# 08_LMS1_RF.net
KiCad netlist of a schematic drawn in Altium Designer
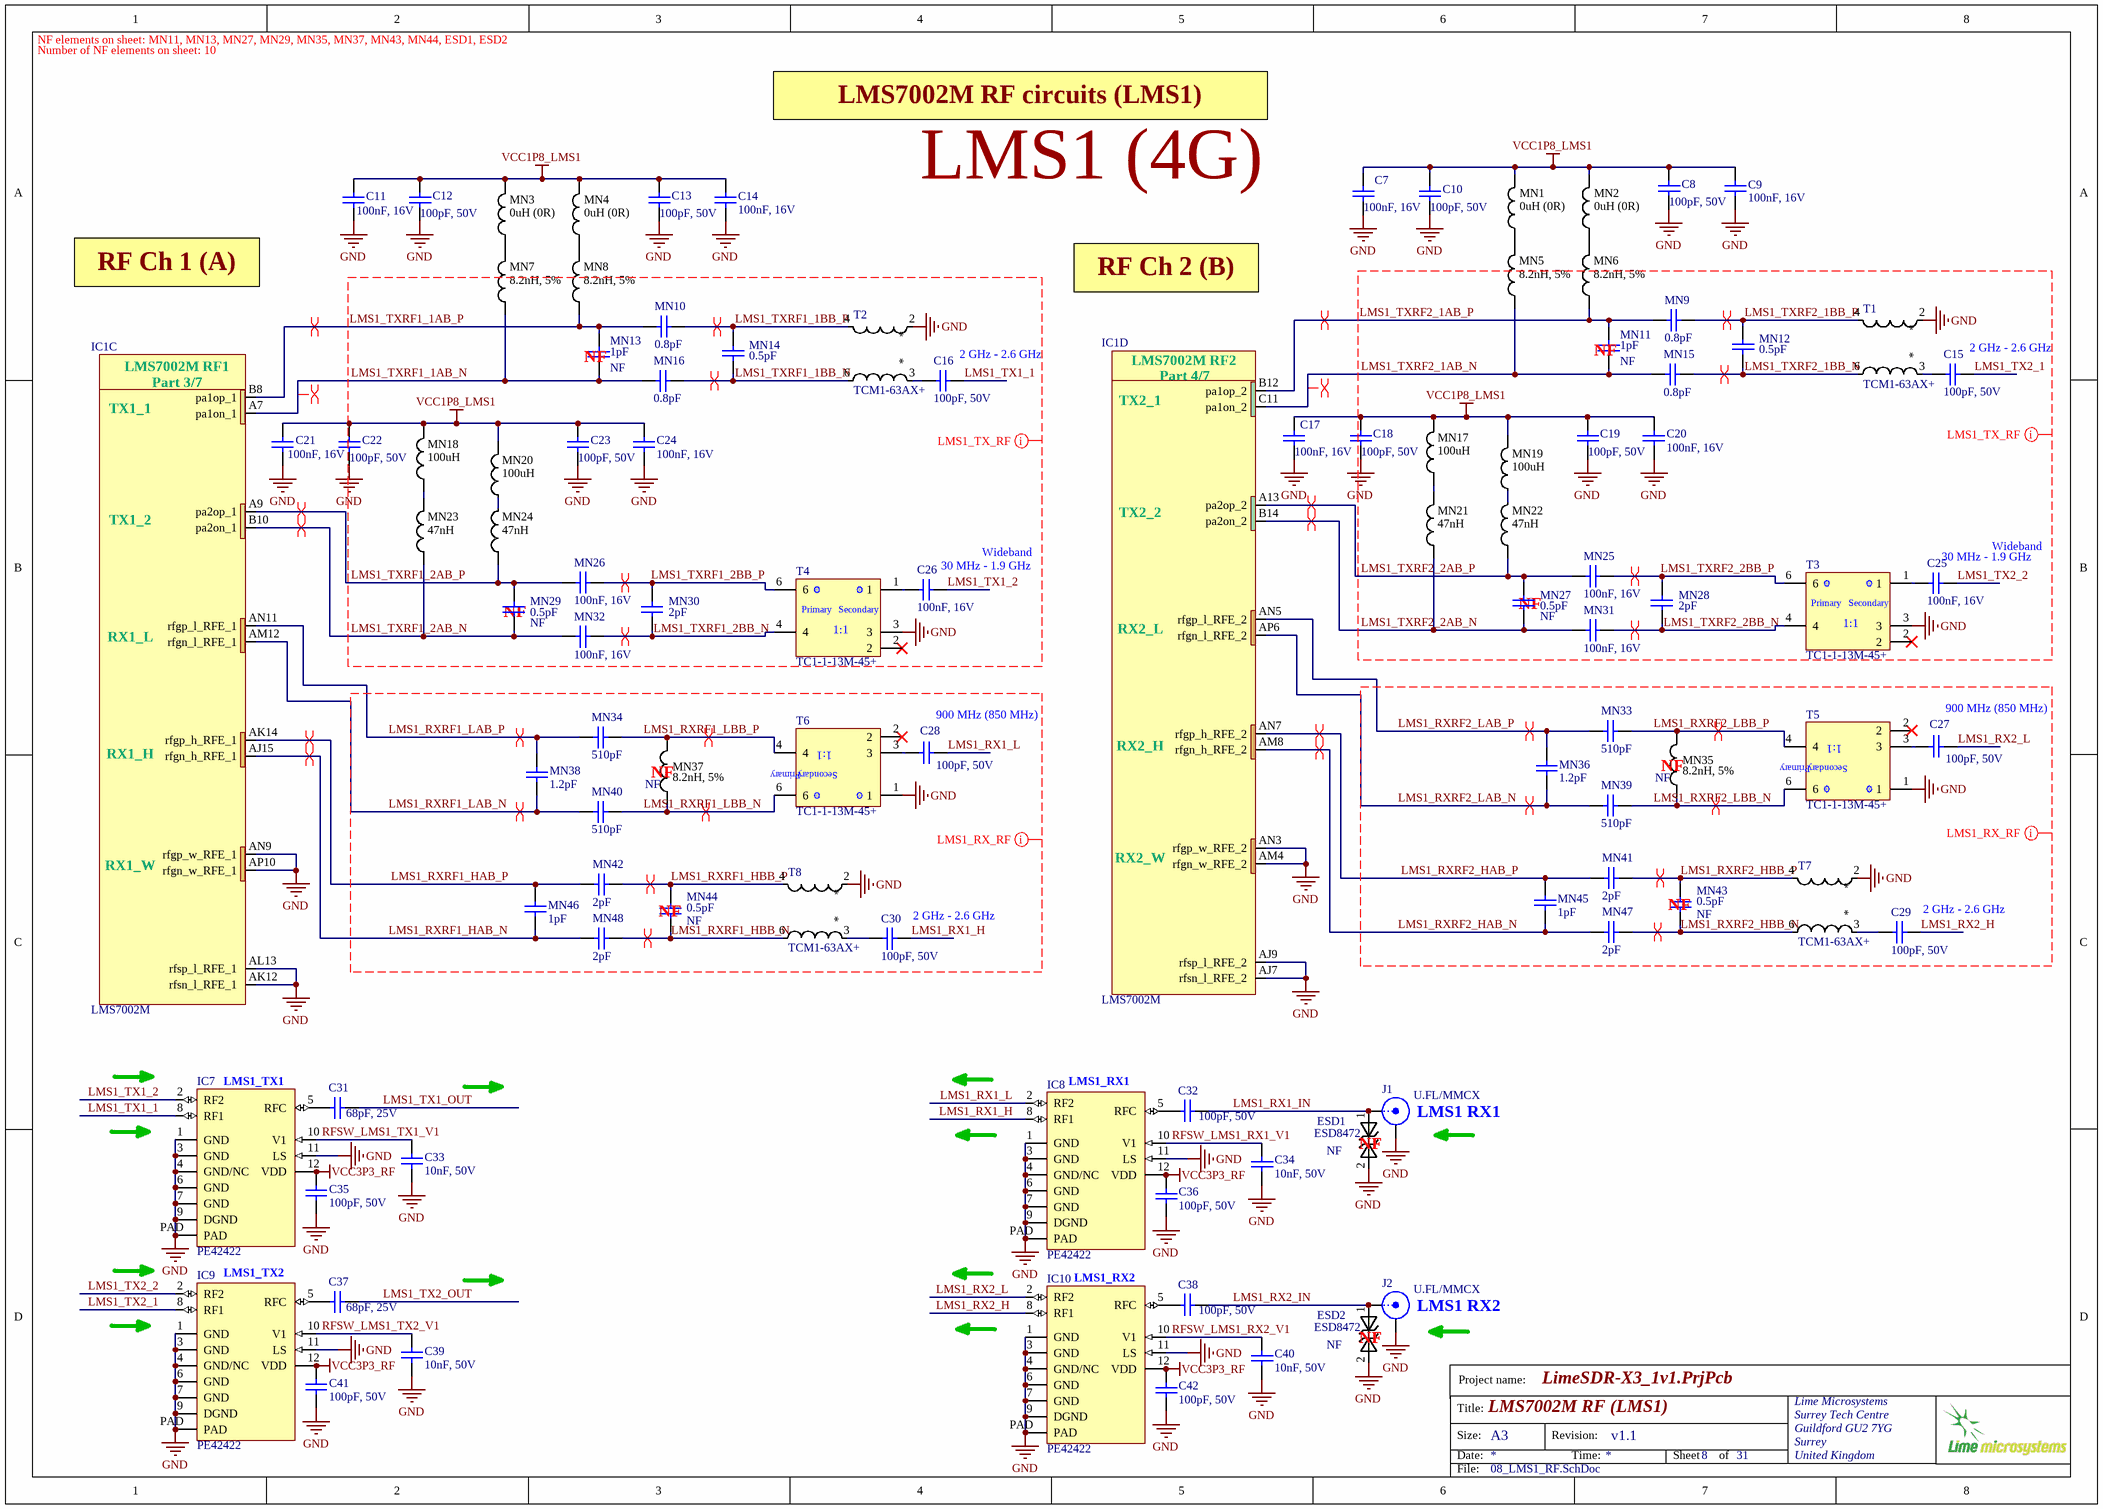
[diagram p0: 08_LMS1_RF.SchDoc]

(export (version "E")
  (design (tool "Eeschema 10.0.6"))
  (components
    (comp (ref "C7")
      (value "100nF, 16V")
      (footprint "CAP0402")
      (fields (field (name "MANUFACTURER") "Murata Electronics") (field (name "TOLERANCE") "10 %"))
      (libsource (lib "") (part "Cap_0402_5"))
    )
    (comp (ref "C8")
      (value "100pF, 50V")
      (footprint "CAP0402")
      (fields (field (name "MANUFACTURER") "Yageo") (field (name "TOLERANCE") "±5%"))
      (libsource (lib "LimeMicroAltiumLib_schLib") (part "Cap_0402"))
    )
    (comp (ref "C9")
      (value "100nF, 16V")
      (footprint "CAP0402")
      (fields (field (name "MANUFACTURER") "Murata Electronics") (field (name "TOLERANCE") "10 %"))
      (libsource (lib "") (part "Cap_0402_5"))
    )
    (comp (ref "C10")
      (value "100pF, 50V")
      (footprint "CAP0402")
      (fields (field (name "MANUFACTURER") "Yageo") (field (name "TOLERANCE") "±5%"))
      (libsource (lib "LimeMicroAltiumLib_schLib") (part "Cap_0402"))
    )
    (comp (ref "C11")
      (value "100nF, 16V")
      (footprint "CAP0402")
      (fields (field (name "MANUFACTURER") "Murata Electronics") (field (name "TOLERANCE") "10 %"))
      (libsource (lib "") (part "Cap_0402_5"))
    )
    (comp (ref "C12")
      (value "100pF, 50V")
      (footprint "CAP0402")
      (fields (field (name "MANUFACTURER") "Yageo") (field (name "TOLERANCE") "±5%"))
      (libsource (lib "LimeMicroAltiumLib_schLib") (part "Cap_0402"))
    )
    (comp (ref "C13")
      (value "100pF, 50V")
      (footprint "CAP0402")
      (fields (field (name "MANUFACTURER") "Yageo") (field (name "TOLERANCE") "±5%"))
      (libsource (lib "LimeMicroAltiumLib_schLib") (part "Cap_0402"))
    )
    (comp (ref "C14")
      (value "100nF, 16V")
      (footprint "CAP0402")
      (fields (field (name "MANUFACTURER") "Murata Electronics") (field (name "TOLERANCE") "10 %"))
      (libsource (lib "") (part "Cap_0402_5"))
    )
    (comp (ref "C15")
      (value "100pF, 50V")
      (footprint "CAP0402")
      (fields (field (name "TOLERANCE") "±5%") (field (name "MANUFACTURER") "Yageo"))
      (libsource (lib "") (part "Cap_0402_1"))
    )
    (comp (ref "C16")
      (value "100pF, 50V")
      (footprint "CAP0402")
      (fields (field (name "TOLERANCE") "±5%") (field (name "MANUFACTURER") "Yageo"))
      (libsource (lib "") (part "Cap_0402_1"))
    )
    (comp (ref "C17")
      (value "100nF, 16V")
      (footprint "CAP0402")
      (fields (field (name "MANUFACTURER") "Murata Electronics") (field (name "TOLERANCE") "10 %"))
      (libsource (lib "") (part "Cap_0402_3"))
    )
    (comp (ref "C18")
      (value "100pF, 50V")
      (footprint "CAP0402")
      (fields (field (name "MANUFACTURER") "Yageo") (field (name "TOLERANCE") "±5%"))
      (libsource (lib "LimeMicroAltiumLib_schLib") (part "Cap_0402"))
    )
    (comp (ref "C19")
      (value "100pF, 50V")
      (footprint "CAP0402")
      (fields (field (name "MANUFACTURER") "Yageo") (field (name "TOLERANCE") "±5%"))
      (libsource (lib "LimeMicroAltiumLib_schLib") (part "Cap_0402"))
    )
    (comp (ref "C20")
      (value "100nF, 16V")
      (footprint "CAP0402")
      (fields (field (name "MANUFACTURER") "Murata Electronics") (field (name "TOLERANCE") "10 %"))
      (libsource (lib "") (part "Cap_0402_3"))
    )
    (comp (ref "C21")
      (value "100nF, 16V")
      (footprint "CAP0402")
      (fields (field (name "MANUFACTURER") "Murata Electronics") (field (name "TOLERANCE") "10 %"))
      (libsource (lib "") (part "Cap_0402_3"))
    )
    (comp (ref "C22")
      (value "100pF, 50V")
      (footprint "CAP0402")
      (fields (field (name "MANUFACTURER") "Yageo") (field (name "TOLERANCE") "±5%"))
      (libsource (lib "LimeMicroAltiumLib_schLib") (part "Cap_0402"))
    )
    (comp (ref "C23")
      (value "100pF, 50V")
      (footprint "CAP0402")
      (fields (field (name "MANUFACTURER") "Yageo") (field (name "TOLERANCE") "±5%"))
      (libsource (lib "LimeMicroAltiumLib_schLib") (part "Cap_0402"))
    )
    (comp (ref "C24")
      (value "100nF, 16V")
      (footprint "CAP0402")
      (fields (field (name "MANUFACTURER") "Murata Electronics") (field (name "TOLERANCE") "10 %"))
      (libsource (lib "") (part "Cap_0402_3"))
    )
    (comp (ref "C25")
      (value "100nF, 16V")
      (footprint "CAP0402")
      (fields (field (name "MANUFACTURER") "Murata Electronics") (field (name "TOLERANCE") "10 %"))
      (libsource (lib "") (part "Cap_0402_9"))
    )
    (comp (ref "C26")
      (value "100nF, 16V")
      (footprint "CAP0402")
      (fields (field (name "MANUFACTURER") "Murata Electronics") (field (name "TOLERANCE") "10 %"))
      (libsource (lib "") (part "Cap_0402_9"))
    )
    (comp (ref "C27")
      (value "100pF, 50V")
      (footprint "CAP0402")
      (fields (field (name "TOLERANCE") "±5%") (field (name "MANUFACTURER") "Yageo"))
      (libsource (lib "") (part "Cap_0402_8"))
    )
    (comp (ref "C28")
      (value "100pF, 50V")
      (footprint "CAP0402")
      (fields (field (name "TOLERANCE") "±5%") (field (name "MANUFACTURER") "Yageo"))
      (libsource (lib "") (part "Cap_0402_8"))
    )
    (comp (ref "C29")
      (value "100pF, 50V")
      (footprint "CAP0402")
      (fields (field (name "TOLERANCE") "±5%") (field (name "MANUFACTURER") "Yageo"))
      (libsource (lib "") (part "Cap_0402_7"))
    )
    (comp (ref "C30")
      (value "100pF, 50V")
      (footprint "CAP0402")
      (fields (field (name "TOLERANCE") "±5%") (field (name "MANUFACTURER") "Yageo"))
      (libsource (lib "") (part "Cap_0402_7"))
    )
    (comp (ref "C31")
      (value "68pF, 25V")
      (footprint "CAP0402")
      (fields (field (name "TOLERANCE") "±1%") (field (name "MANUFACTURER") "Kemet"))
      (libsource (lib "") (part "Cap_0402_1"))
    )
    (comp (ref "C32")
      (value "100pF, 50V")
      (footprint "CAP0402")
      (fields (field (name "TOLERANCE") "±5%") (field (name "MANUFACTURER") "Yageo"))
      (libsource (lib "") (part "Cap_0402_6"))
    )
    (comp (ref "C33")
      (value "10nF, 50V")
      (footprint "CAP0402")
      (fields
        (field (name "MANUFACTURER") "Murata Electronics North America")
        (field (name "TOLERANCE") "±10%")
      )
      (libsource (lib "") (part "Cap_0402_5"))
    )
    (comp (ref "C34")
      (value "10nF, 50V")
      (footprint "CAP0402")
      (fields
        (field (name "MANUFACTURER") "Murata Electronics North America")
        (field (name "TOLERANCE") "±10%")
      )
      (libsource (lib "") (part "Cap_0402_3"))
    )
    (comp (ref "C35")
      (value "100pF, 50V")
      (footprint "CAP0402")
      (fields (field (name "TOLERANCE") "±5%") (field (name "MANUFACTURER") "Yageo"))
      (libsource (lib "") (part "Cap_0402_5"))
    )
    (comp (ref "C36")
      (value "100pF, 50V")
      (footprint "CAP0402")
      (fields (field (name "TOLERANCE") "±5%") (field (name "MANUFACTURER") "Yageo"))
      (libsource (lib "") (part "Cap_0402_11"))
    )
    (comp (ref "C37")
      (value "68pF, 25V")
      (footprint "CAP0402")
      (fields (field (name "TOLERANCE") "±1%") (field (name "MANUFACTURER") "Kemet"))
      (libsource (lib "") (part "Cap_0402_1"))
    )
    (comp (ref "C38")
      (value "100pF, 50V")
      (footprint "CAP0402")
      (fields (field (name "TOLERANCE") "±5%") (field (name "MANUFACTURER") "Yageo"))
      (libsource (lib "") (part "Cap_0402_6"))
    )
    (comp (ref "C39")
      (value "10nF, 50V")
      (footprint "CAP0402")
      (fields
        (field (name "MANUFACTURER") "Murata Electronics North America")
        (field (name "TOLERANCE") "±10%")
      )
      (libsource (lib "") (part "Cap_0402_5"))
    )
    (comp (ref "C40")
      (value "10nF, 50V")
      (footprint "CAP0402")
      (fields
        (field (name "MANUFACTURER") "Murata Electronics North America")
        (field (name "TOLERANCE") "±10%")
      )
      (libsource (lib "") (part "Cap_0402_3"))
    )
    (comp (ref "C41")
      (value "100pF, 50V")
      (footprint "CAP0402")
      (fields (field (name "TOLERANCE") "±5%") (field (name "MANUFACTURER") "Yageo"))
      (libsource (lib "") (part "Cap_0402_5"))
    )
    (comp (ref "C42")
      (value "100pF, 50V")
      (footprint "CAP0402")
      (fields (field (name "TOLERANCE") "±5%") (field (name "MANUFACTURER") "Yageo"))
      (libsource (lib "") (part "Cap_0402_11"))
    )
    (comp (ref "ESD1")
      (value "ESD8472")
      (footprint "ESD8472_X3DFN2")
      (fields (field (name "MANUFACTURER") "ON Semiconductor") (field (name "ASSEMBLY INFO") "NF"))
      (libsource (lib "LimeMicroAltiumLib_schLib") (part "ESD8472"))
    )
    (comp (ref "ESD2")
      (value "ESD8472")
      (footprint "ESD8472_X3DFN2")
      (fields (field (name "MANUFACTURER") "ON Semiconductor") (field (name "ASSEMBLY INFO") "NF"))
      (libsource (lib "LimeMicroAltiumLib_schLib") (part "ESD8472"))
    )
    (comp (ref "IC1")
      (value "LMS7002M")
      (footprint "LMS7002M_v5")
      (description "Schematic symbol revision 4. Default footprint - 0.31mm pad")
      (fields (field (name "MANUFACTURER") "Lime Microsystems"))
      (libsource (lib "LimeMicroAltiumLib_schLib_r04") (part "LMS7002Mr4"))
    )
    (comp (ref "IC7")
      (value "PE42422")
      (footprint "PE42422_QFN12")
      (fields (field (name "MANUFACTURER") "Peregrine Semiconductor"))
      (libsource (lib "LimeMicroAltiumLib_schLib") (part "PE42422"))
    )
    (comp (ref "IC8")
      (value "PE42422")
      (footprint "PE42422_QFN12")
      (fields (field (name "MANUFACTURER") "Peregrine Semiconductor"))
      (libsource (lib "") (part "PE42422_1"))
    )
    (comp (ref "IC9")
      (value "PE42422")
      (footprint "PE42422_QFN12")
      (fields (field (name "MANUFACTURER") "Peregrine Semiconductor"))
      (libsource (lib "LimeMicroAltiumLib_schLib") (part "PE42422"))
    )
    (comp (ref "IC10")
      (value "PE42422")
      (footprint "PE42422_QFN12")
      (fields (field (name "MANUFACTURER") "Peregrine Semiconductor"))
      (libsource (lib "") (part "PE42422_1"))
    )
    (comp (ref "J1")
      (value "U.FL/MMCX")
      (footprint "MMCX_UFL_conn_m")
      (description "CONN UMC RCPT STR 50 OHM SMD")
      (fields (field (name "MANUFACTURER") "Amphenol RF"))
      (libsource (lib "LimeMicroAltiumLib_schLib") (part "RF_IF_connector"))
    )
    (comp (ref "J2")
      (value "U.FL/MMCX")
      (footprint "MMCX_UFL_conn_m")
      (description "CONN UMC RCPT STR 50 OHM SMD")
      (fields (field (name "MANUFACTURER") "Amphenol RF"))
      (libsource (lib "LimeMicroAltiumLib_schLib") (part "RF_IF_connector"))
    )
    (comp (ref "MN1")
      (value "0uH (0R)")
      (footprint "RES0603")
      (fields
        (field (name "MANUFACTURER") "Panasonic Electronic Components")
        (field (name "MANUFACTURER PART NUMBER") "ERJ-3GEY0R00V")
        (field (name "TOLERANCE") "Jumper")
      )
      (libsource (lib "") (part "Inductor_0603_1"))
    )
    (comp (ref "MN2")
      (value "0uH (0R)")
      (footprint "RES0603")
      (fields
        (field (name "MANUFACTURER") "Panasonic Electronic Components")
        (field (name "MANUFACTURER PART NUMBER") "ERJ-3GEY0R00V")
        (field (name "TOLERANCE") "Jumper")
      )
      (libsource (lib "") (part "Inductor_0603_1"))
    )
    (comp (ref "MN3")
      (value "0uH (0R)")
      (footprint "RES0603")
      (fields
        (field (name "MANUFACTURER") "Panasonic Electronic Components")
        (field (name "MANUFACTURER PART NUMBER") "ERJ-3GEY0R00V")
        (field (name "TOLERANCE") "Jumper")
      )
      (libsource (lib "") (part "Inductor_0603_1"))
    )
    (comp (ref "MN4")
      (value "0uH (0R)")
      (footprint "RES0603")
      (fields
        (field (name "MANUFACTURER") "Panasonic Electronic Components")
        (field (name "MANUFACTURER PART NUMBER") "ERJ-3GEY0R00V")
        (field (name "TOLERANCE") "Jumper")
      )
      (libsource (lib "") (part "Inductor_0603_1"))
    )
    (comp (ref "MN5")
      (value "8.2nH, 5%")
      (footprint "RES0402")
      (fields (field (name "MANUFACTURER") "COILCRAFT"))
      (libsource (lib "") (part "Inductor_0603_2"))
    )
    (comp (ref "MN6")
      (value "8.2nH, 5%")
      (footprint "RES0402")
      (fields (field (name "MANUFACTURER") "COILCRAFT"))
      (libsource (lib "") (part "Inductor_0603_2"))
    )
    (comp (ref "MN7")
      (value "8.2nH, 5%")
      (footprint "RES0402")
      (fields (field (name "MANUFACTURER") "COILCRAFT"))
      (libsource (lib "") (part "Inductor_0603_2"))
    )
    (comp (ref "MN8")
      (value "8.2nH, 5%")
      (footprint "RES0402")
      (fields (field (name "MANUFACTURER") "COILCRAFT"))
      (libsource (lib "") (part "Inductor_0603_2"))
    )
    (comp (ref "MN9")
      (value "0.8pF")
      (footprint "CAP0402")
      (fields
        (field (name "TOLERANCE") "±0.1pF")
        (field (name "MANUFACTURER") "Murata Electronics North America")
        (field (name "MANUFACTURER PART NUMBER") "GRM1555C1HR80BA01D")
      )
      (libsource (lib "") (part "Cap_0402_4"))
    )
    (comp (ref "MN10")
      (value "0.8pF")
      (footprint "CAP0402")
      (fields
        (field (name "TOLERANCE") "±0.1pF")
        (field (name "MANUFACTURER") "Murata Electronics North America")
        (field (name "MANUFACTURER PART NUMBER") "GRM1555C1HR80BA01D")
      )
      (libsource (lib "") (part "Cap_0402_4"))
    )
    (comp (ref "MN11")
      (value "1pF")
      (footprint "CAP0402")
      (fields
        (field (name "ASSEMBLY INFO") "NF")
        (field (name "MANUFACTURER") "TDK Corporation")
        (field (name "TOLERANCE") "±0.1pF")
      )
      (libsource (lib "") (part "Cap_0402_8"))
    )
    (comp (ref "MN12")
      (value "0.5pF")
      (footprint "CAP0402")
      (fields (field (name "TOLERANCE") "±0.25pF") (field (name "MANUFACTURER") "Yageo"))
      (libsource (lib "") (part "Cap_0402_2"))
    )
    (comp (ref "MN13")
      (value "1pF")
      (footprint "CAP0402")
      (fields
        (field (name "ASSEMBLY INFO") "NF")
        (field (name "MANUFACTURER") "TDK Corporation")
        (field (name "TOLERANCE") "±0.1pF")
      )
      (libsource (lib "") (part "Cap_0402_8"))
    )
    (comp (ref "MN14")
      (value "0.5pF")
      (footprint "CAP0402")
      (fields (field (name "TOLERANCE") "±0.25pF") (field (name "MANUFACTURER") "Yageo"))
      (libsource (lib "") (part "Cap_0402_2"))
    )
    (comp (ref "MN15")
      (value "0.8pF")
      (footprint "CAP0402")
      (fields
        (field (name "TOLERANCE") "±0.1pF")
        (field (name "MANUFACTURER") "Murata Electronics North America")
        (field (name "MANUFACTURER PART NUMBER") "GRM1555C1HR80BA01D")
      )
      (libsource (lib "") (part "Cap_0402_4"))
    )
    (comp (ref "MN16")
      (value "0.8pF")
      (footprint "CAP0402")
      (fields
        (field (name "TOLERANCE") "±0.1pF")
        (field (name "MANUFACTURER") "Murata Electronics North America")
        (field (name "MANUFACTURER PART NUMBER") "GRM1555C1HR80BA01D")
      )
      (libsource (lib "") (part "Cap_0402_4"))
    )
    (comp (ref "MN17")
      (value "100uH")
      (footprint "RES0603")
      (fields
        (field (name "MANUFACTURER") "TDK Corporation")
        (field (name "MANUFACTURER PART NUMBER") "GLFR1608T101M-LR")
        (field (name "TOLERANCE") "±20%")
      )
      (libsource (lib "") (part "Inductor_0603_1"))
    )
    (comp (ref "MN18")
      (value "100uH")
      (footprint "RES0603")
      (fields
        (field (name "MANUFACTURER") "TDK Corporation")
        (field (name "MANUFACTURER PART NUMBER") "GLFR1608T101M-LR")
        (field (name "TOLERANCE") "±20%")
      )
      (libsource (lib "") (part "Inductor_0603_1"))
    )
    (comp (ref "MN19")
      (value "100uH")
      (footprint "RES0603")
      (fields
        (field (name "MANUFACTURER") "TDK Corporation")
        (field (name "MANUFACTURER PART NUMBER") "GLFR1608T101M-LR")
        (field (name "TOLERANCE") "±20%")
      )
      (libsource (lib "") (part "Inductor_0603_1"))
    )
    (comp (ref "MN20")
      (value "100uH")
      (footprint "RES0603")
      (fields
        (field (name "MANUFACTURER") "TDK Corporation")
        (field (name "MANUFACTURER PART NUMBER") "GLFR1608T101M-LR")
        (field (name "TOLERANCE") "±20%")
      )
      (libsource (lib "") (part "Inductor_0603_1"))
    )
    (comp (ref "MN21")
      (value "47nH")
      (footprint "RES0402")
      (fields (field (name "MANUFACTURER") "COILCRAFT"))
      (libsource (lib "LimeMicroAltiumLib_schLib") (part "Inductor_0603"))
    )
    (comp (ref "MN22")
      (value "47nH")
      (footprint "RES0402")
      (fields (field (name "MANUFACTURER") "COILCRAFT"))
      (libsource (lib "LimeMicroAltiumLib_schLib") (part "Inductor_0603"))
    )
    (comp (ref "MN23")
      (value "47nH")
      (footprint "RES0402")
      (fields (field (name "MANUFACTURER") "COILCRAFT"))
      (libsource (lib "LimeMicroAltiumLib_schLib") (part "Inductor_0603"))
    )
    (comp (ref "MN24")
      (value "47nH")
      (footprint "RES0402")
      (fields (field (name "MANUFACTURER") "COILCRAFT"))
      (libsource (lib "LimeMicroAltiumLib_schLib") (part "Inductor_0603"))
    )
    (comp (ref "MN25")
      (value "100nF, 16V")
      (footprint "CAP0402")
      (fields (field (name "MANUFACTURER") "Murata Electronics") (field (name "TOLERANCE") "10 %"))
      (libsource (lib "LimeMicroAltiumLib_schLib") (part "Cap_0402"))
    )
    (comp (ref "MN26")
      (value "100nF, 16V")
      (footprint "CAP0402")
      (fields (field (name "MANUFACTURER") "Murata Electronics") (field (name "TOLERANCE") "10 %"))
      (libsource (lib "LimeMicroAltiumLib_schLib") (part "Cap_0402"))
    )
    (comp (ref "MN27")
      (value "0.5pF")
      (footprint "CAP0402")
      (fields
        (field (name "ASSEMBLY INFO") "NF")
        (field (name "TOLERANCE") "±0.25pF")
        (field (name "MANUFACTURER") "Yageo")
      )
      (libsource (lib "") (part "Cap_0402_3"))
    )
    (comp (ref "MN28")
      (value "2pF")
      (footprint "CAP0402")
      (fields (field (name "MANUFACTURER PART NUMBER") "04025U2R0BAT2A") (field (name "MANUFACTURER") "AVX"))
      (libsource (lib "") (part "Cap_0402_3"))
    )
    (comp (ref "MN29")
      (value "0.5pF")
      (footprint "CAP0402")
      (fields
        (field (name "ASSEMBLY INFO") "NF")
        (field (name "TOLERANCE") "±0.25pF")
        (field (name "MANUFACTURER") "Yageo")
      )
      (libsource (lib "") (part "Cap_0402_3"))
    )
    (comp (ref "MN30")
      (value "2pF")
      (footprint "CAP0402")
      (fields (field (name "MANUFACTURER PART NUMBER") "04025U2R0BAT2A") (field (name "MANUFACTURER") "AVX"))
      (libsource (lib "") (part "Cap_0402_3"))
    )
    (comp (ref "MN31")
      (value "100nF, 16V")
      (footprint "CAP0402")
      (fields (field (name "MANUFACTURER") "Murata Electronics") (field (name "TOLERANCE") "10 %"))
      (libsource (lib "") (part "Cap_0402_2"))
    )
    (comp (ref "MN32")
      (value "100nF, 16V")
      (footprint "CAP0402")
      (fields (field (name "MANUFACTURER") "Murata Electronics") (field (name "TOLERANCE") "10 %"))
      (libsource (lib "") (part "Cap_0402_2"))
    )
    (comp (ref "MN33")
      (value "510pF")
      (footprint "CAP0402")
      (fields
        (field (name "TOLERANCE") "±5%")
        (field (name "MANUFACTURER") "Murata Electronics North America")
      )
      (libsource (lib "") (part "Cap_0402_5"))
    )
    (comp (ref "MN34")
      (value "510pF")
      (footprint "CAP0402")
      (fields
        (field (name "TOLERANCE") "±5%")
        (field (name "MANUFACTURER") "Murata Electronics North America")
      )
      (libsource (lib "") (part "Cap_0402_5"))
    )
    (comp (ref "MN35")
      (value "8.2nH, 5%")
      (footprint "RES0402")
      (fields (field (name "MANUFACTURER") "COILCRAFT") (field (name "ASSEMBLY INFO") "NF"))
      (libsource (lib "LimeMicroAltiumLib_schLib") (part "Inductor_0603"))
    )
    (comp (ref "MN36")
      (value "1.2pF")
      (footprint "CAP0402")
      (fields
        (field (name "MANUFACTURER") "Murata Electronics North America")
        (field (name "TOLERANCE") "±0.25pF")
      )
      (libsource (lib "") (part "Cap_0402_10"))
    )
    (comp (ref "MN37")
      (value "8.2nH, 5%")
      (footprint "RES0402")
      (fields (field (name "MANUFACTURER") "COILCRAFT") (field (name "ASSEMBLY INFO") "NF"))
      (libsource (lib "LimeMicroAltiumLib_schLib") (part "Inductor_0603"))
    )
    (comp (ref "MN38")
      (value "1.2pF")
      (footprint "CAP0402")
      (fields
        (field (name "MANUFACTURER") "Murata Electronics North America")
        (field (name "TOLERANCE") "±0.25pF")
      )
      (libsource (lib "") (part "Cap_0402_10"))
    )
    (comp (ref "MN39")
      (value "510pF")
      (footprint "CAP0402")
      (fields
        (field (name "TOLERANCE") "±5%")
        (field (name "MANUFACTURER") "Murata Electronics North America")
      )
      (libsource (lib "") (part "Cap_0402_5"))
    )
    (comp (ref "MN40")
      (value "510pF")
      (footprint "CAP0402")
      (fields
        (field (name "TOLERANCE") "±5%")
        (field (name "MANUFACTURER") "Murata Electronics North America")
      )
      (libsource (lib "") (part "Cap_0402_5"))
    )
    (comp (ref "MN41")
      (value "2pF")
      (footprint "CAP0402")
      (fields (field (name "MANUFACTURER PART NUMBER") "04025U2R0BAT2A") (field (name "MANUFACTURER") "AVX"))
      (libsource (lib "") (part "Cap_0402_4"))
    )
    (comp (ref "MN42")
      (value "2pF")
      (footprint "CAP0402")
      (fields (field (name "MANUFACTURER PART NUMBER") "04025U2R0BAT2A") (field (name "MANUFACTURER") "AVX"))
      (libsource (lib "") (part "Cap_0402_4"))
    )
    (comp (ref "MN43")
      (value "0.5pF")
      (footprint "CAP0402")
      (fields
        (field (name "ASSEMBLY INFO") "NF")
        (field (name "TOLERANCE") "±0.25pF")
        (field (name "MANUFACTURER") "Yageo")
      )
      (libsource (lib "") (part "Cap_0402_4"))
    )
    (comp (ref "MN44")
      (value "0.5pF")
      (footprint "CAP0402")
      (fields
        (field (name "ASSEMBLY INFO") "NF")
        (field (name "TOLERANCE") "±0.25pF")
        (field (name "MANUFACTURER") "Yageo")
      )
      (libsource (lib "") (part "Cap_0402_4"))
    )
    (comp (ref "MN45")
      (value "1pF")
      (footprint "CAP0402")
      (fields (field (name "MANUFACTURER") "TDK Corporation") (field (name "TOLERANCE") "±0.1pF"))
      (libsource (lib "") (part "Cap_0402_4"))
    )
    (comp (ref "MN46")
      (value "1pF")
      (footprint "CAP0402")
      (fields (field (name "MANUFACTURER") "TDK Corporation") (field (name "TOLERANCE") "±0.1pF"))
      (libsource (lib "") (part "Cap_0402_4"))
    )
    (comp (ref "MN47")
      (value "2pF")
      (footprint "CAP0402")
      (fields (field (name "MANUFACTURER PART NUMBER") "04025U2R0BAT2A") (field (name "MANUFACTURER") "AVX"))
      (libsource (lib "") (part "Cap_0402_4"))
    )
    (comp (ref "MN48")
      (value "2pF")
      (footprint "CAP0402")
      (fields (field (name "MANUFACTURER PART NUMBER") "04025U2R0BAT2A") (field (name "MANUFACTURER") "AVX"))
      (libsource (lib "") (part "Cap_0402_4"))
    )
    (comp (ref "T1")
      (value "TCM1-63AX+")
      (footprint "TCM1-63AX+_v2")
      (fields (field (name "MANUFACTURER") "Mini-circuits"))
      (libsource (lib "") (part "Balun_v2_1"))
    )
    (comp (ref "T2")
      (value "TCM1-63AX+")
      (footprint "TCM1-63AX+_v2")
      (fields (field (name "MANUFACTURER") "Mini-circuits"))
      (libsource (lib "") (part "Balun_v2_1"))
    )
    (comp (ref "T3")
      (value "TC1-1-13M-45+")
      (footprint "TC1-1-13MA+_JA4220-AL_")
      (fields (field (name "MANUFACTURER") "Minicircuits"))
      (libsource (lib "") (part "TC1-1-13M+_1"))
    )
    (comp (ref "T4")
      (value "TC1-1-13M-45+")
      (footprint "TC1-1-13MA+_JA4220-AL_")
      (fields (field (name "MANUFACTURER") "Minicircuits"))
      (libsource (lib "") (part "TC1-1-13M+_1"))
    )
    (comp (ref "T5")
      (value "TC1-1-13M-45+")
      (footprint "TC1-1-13MA+_JA4220-AL_")
      (fields (field (name "MANUFACTURER") "Minicircuits"))
      (libsource (lib "LimeMicroAltiumLib_schLib") (part "TC1-1-13M+"))
    )
    (comp (ref "T6")
      (value "TC1-1-13M-45+")
      (footprint "TC1-1-13MA+_JA4220-AL_")
      (fields (field (name "MANUFACTURER") "Minicircuits"))
      (libsource (lib "LimeMicroAltiumLib_schLib") (part "TC1-1-13M+"))
    )
    (comp (ref "T7")
      (value "TCM1-63AX+")
      (footprint "TCM1-63AX+_v2")
      (fields (field (name "MANUFACTURER") "Mini-circuits"))
      (libsource (lib "LimeMicroAltiumLib_schLib") (part "Balun_v2"))
    )
    (comp (ref "T8")
      (value "TCM1-63AX+")
      (footprint "TCM1-63AX+_v2")
      (fields (field (name "MANUFACTURER") "Mini-circuits"))
      (libsource (lib "LimeMicroAltiumLib_schLib") (part "Balun_v2"))
    )
  )
  (nets
    (net (code "1") (name "/LMS1_RX1_H") (class "Default")
      (node (ref "C30") (pin "1") (pinfunction "1_1") (pintype "passive"))
      (node (ref "IC8") (pin "8") (pinfunction "RF1_8") (pintype "bidirectional"))
    )
    (net (code "2") (name "/LMS1_RX1_IN") (class "Default")
      (node (ref "C32") (pin "1") (pinfunction "1_1") (pintype "passive"))
      (node (ref "ESD1") (pin "1") (pinfunction "1_1") (pintype "passive"))
      (node (ref "J1") (pin "1") (pinfunction "X_1") (pintype "passive"))
    )
    (net (code "3") (name "/LMS1_RX1_L") (class "Default")
      (node (ref "C28") (pin "1") (pinfunction "1_1") (pintype "passive"))
      (node (ref "IC8") (pin "2") (pinfunction "RF2_2") (pintype "bidirectional"))
    )
    (net (code "4") (name "/LMS1_RX2_H") (class "Default")
      (node (ref "C29") (pin "1") (pinfunction "1_1") (pintype "passive"))
      (node (ref "IC10") (pin "8") (pinfunction "RF1_8") (pintype "bidirectional"))
    )
    (net (code "5") (name "/LMS1_RX2_IN") (class "Default")
      (node (ref "C38") (pin "1") (pinfunction "1_1") (pintype "passive"))
      (node (ref "ESD2") (pin "1") (pinfunction "1_1") (pintype "passive"))
      (node (ref "J2") (pin "1") (pinfunction "X_1") (pintype "passive"))
    )
    (net (code "6") (name "/LMS1_RX2_L") (class "Default")
      (node (ref "C27") (pin "1") (pinfunction "1_1") (pintype "passive"))
      (node (ref "IC10") (pin "2") (pinfunction "RF2_2") (pintype "bidirectional"))
    )
    (net (code "7") (name "/LMS1_RXRF1_HAB_N") (class "Default")
      (node (ref "IC1") (pin "AJ15") (pinfunction "rfgn_h_RFE_1_AJ15") (pintype "passive"))
      (node (ref "MN46") (pin "1") (pinfunction "1_1") (pintype "passive"))
      (node (ref "MN48") (pin "2") (pinfunction "2_2") (pintype "passive"))
    )
    (net (code "8") (name "/LMS1_RXRF1_HAB_P") (class "Default")
      (node (ref "IC1") (pin "AK14") (pinfunction "rfgp_h_RFE_1_AK14") (pintype "passive"))
      (node (ref "MN42") (pin "2") (pinfunction "2_2") (pintype "passive"))
      (node (ref "MN46") (pin "2") (pinfunction "2_2") (pintype "passive"))
    )
    (net (code "9") (name "/LMS1_RXRF1_HBB_N") (class "Default")
      (node (ref "MN44") (pin "1") (pinfunction "1_1") (pintype "passive"))
      (node (ref "MN48") (pin "1") (pinfunction "1_1") (pintype "passive"))
      (node (ref "T8") (pin "6") (pinfunction "6_6") (pintype "passive"))
    )
    (net (code "10") (name "/LMS1_RXRF1_HBB_P") (class "Default")
      (node (ref "MN42") (pin "1") (pinfunction "1_1") (pintype "passive"))
      (node (ref "MN44") (pin "2") (pinfunction "2_2") (pintype "passive"))
      (node (ref "T8") (pin "4") (pinfunction "4_4") (pintype "passive"))
    )
    (net (code "11") (name "/LMS1_RXRF1_LAB_N") (class "Default")
      (node (ref "IC1") (pin "AM12") (pinfunction "rfgn_l_RFE_1_AM12") (pintype "passive"))
      (node (ref "MN38") (pin "1") (pinfunction "1_1") (pintype "passive"))
      (node (ref "MN40") (pin "2") (pinfunction "2_2") (pintype "passive"))
    )
    (net (code "12") (name "/LMS1_RXRF1_LAB_P") (class "Default")
      (node (ref "IC1") (pin "AN11") (pinfunction "rfgp_l_RFE_1_AN11") (pintype "passive"))
      (node (ref "MN34") (pin "2") (pinfunction "2_2") (pintype "passive"))
      (node (ref "MN38") (pin "2") (pinfunction "2_2") (pintype "passive"))
    )
    (net (code "13") (name "/LMS1_RXRF1_LBB_N") (class "Default")
      (node (ref "MN37") (pin "1") (pinfunction "1_1") (pintype "passive"))
      (node (ref "MN40") (pin "1") (pinfunction "1_1") (pintype "passive"))
      (node (ref "T6") (pin "6") (pinfunction "6_6") (pintype "passive"))
    )
    (net (code "14") (name "/LMS1_RXRF1_LBB_P") (class "Default")
      (node (ref "MN34") (pin "1") (pinfunction "1_1") (pintype "passive"))
      (node (ref "MN37") (pin "2") (pinfunction "2_2") (pintype "passive"))
      (node (ref "T6") (pin "4") (pinfunction "4_4") (pintype "passive"))
    )
    (net (code "15") (name "/LMS1_RXRF2_HAB_N") (class "Default")
      (node (ref "IC1") (pin "AM8") (pinfunction "rfgn_h_RFE_2_AM8") (pintype "passive"))
      (node (ref "MN45") (pin "1") (pinfunction "1_1") (pintype "passive"))
      (node (ref "MN47") (pin "2") (pinfunction "2_2") (pintype "passive"))
    )
    (net (code "16") (name "/LMS1_RXRF2_HAB_P") (class "Default")
      (node (ref "IC1") (pin "AN7") (pinfunction "rfgp_h_RFE_2_AN7") (pintype "passive"))
      (node (ref "MN41") (pin "2") (pinfunction "2_2") (pintype "passive"))
      (node (ref "MN45") (pin "2") (pinfunction "2_2") (pintype "passive"))
    )
    (net (code "17") (name "/LMS1_RXRF2_HBB_N") (class "Default")
      (node (ref "MN43") (pin "1") (pinfunction "1_1") (pintype "passive"))
      (node (ref "MN47") (pin "1") (pinfunction "1_1") (pintype "passive"))
      (node (ref "T7") (pin "6") (pinfunction "6_6") (pintype "passive"))
    )
    (net (code "18") (name "/LMS1_RXRF2_HBB_P") (class "Default")
      (node (ref "MN41") (pin "1") (pinfunction "1_1") (pintype "passive"))
      (node (ref "MN43") (pin "2") (pinfunction "2_2") (pintype "passive"))
      (node (ref "T7") (pin "4") (pinfunction "4_4") (pintype "passive"))
    )
    (net (code "19") (name "/LMS1_RXRF2_LAB_N") (class "Default")
      (node (ref "IC1") (pin "AP6") (pinfunction "rfgn_l_RFE_2_AP6") (pintype "passive"))
      (node (ref "MN36") (pin "1") (pinfunction "1_1") (pintype "passive"))
      (node (ref "MN39") (pin "2") (pinfunction "2_2") (pintype "passive"))
    )
    (net (code "20") (name "/LMS1_RXRF2_LAB_P") (class "Default")
      (node (ref "IC1") (pin "AN5") (pinfunction "rfgp_l_RFE_2_AN5") (pintype "passive"))
      (node (ref "MN33") (pin "2") (pinfunction "2_2") (pintype "passive"))
      (node (ref "MN36") (pin "2") (pinfunction "2_2") (pintype "passive"))
    )
    (net (code "21") (name "/LMS1_RXRF2_LBB_N") (class "Default")
      (node (ref "MN35") (pin "1") (pinfunction "1_1") (pintype "passive"))
      (node (ref "MN39") (pin "1") (pinfunction "1_1") (pintype "passive"))
      (node (ref "T5") (pin "6") (pinfunction "6_6") (pintype "passive"))
    )
    (net (code "22") (name "/LMS1_RXRF2_LBB_P") (class "Default")
      (node (ref "MN33") (pin "1") (pinfunction "1_1") (pintype "passive"))
      (node (ref "MN35") (pin "2") (pinfunction "2_2") (pintype "passive"))
      (node (ref "T5") (pin "4") (pinfunction "4_4") (pintype "passive"))
    )
    (net (code "23") (name "/LMS1_TX1_1") (class "Default")
      (node (ref "C16") (pin "1") (pinfunction "1_1") (pintype "passive"))
      (node (ref "IC7") (pin "8") (pinfunction "RF1_8") (pintype "bidirectional"))
    )
    (net (code "24") (name "/LMS1_TX1_2") (class "Default")
      (node (ref "C26") (pin "1") (pinfunction "1_1") (pintype "passive"))
      (node (ref "IC7") (pin "2") (pinfunction "RF2_2") (pintype "bidirectional"))
    )
    (net (code "25") (name "/LMS1_TX1_OUT") (class "Default")
      (node (ref "C31") (pin "2") (pinfunction "2_2") (pintype "passive"))
    )
    (net (code "26") (name "/LMS1_TX2_1") (class "Default")
      (node (ref "C15") (pin "1") (pinfunction "1_1") (pintype "passive"))
      (node (ref "IC9") (pin "8") (pinfunction "RF1_8") (pintype "bidirectional"))
    )
    (net (code "27") (name "/LMS1_TX2_2") (class "Default")
      (node (ref "C25") (pin "1") (pinfunction "1_1") (pintype "passive"))
      (node (ref "IC9") (pin "2") (pinfunction "RF2_2") (pintype "bidirectional"))
    )
    (net (code "28") (name "/LMS1_TX2_OUT") (class "Default")
      (node (ref "C37") (pin "2") (pinfunction "2_2") (pintype "passive"))
    )
    (net (code "29") (name "/LMS1_TXRF1_1AB_N") (class "Default")
      (node (ref "IC1") (pin "A7") (pinfunction "pa1on_1_A7") (pintype "passive"))
      (node (ref "MN13") (pin "2") (pinfunction "2_2") (pintype "passive"))
      (node (ref "MN16") (pin "2") (pinfunction "2_2") (pintype "passive"))
      (node (ref "MN7") (pin "1") (pinfunction "1_1") (pintype "passive"))
    )
    (net (code "30") (name "/LMS1_TXRF1_1AB_P") (class "Default")
      (node (ref "IC1") (pin "B8") (pinfunction "pa1op_1_B8") (pintype "passive"))
      (node (ref "MN10") (pin "2") (pinfunction "2_2") (pintype "passive"))
      (node (ref "MN13") (pin "1") (pinfunction "1_1") (pintype "passive"))
      (node (ref "MN8") (pin "1") (pinfunction "1_1") (pintype "passive"))
    )
    (net (code "31") (name "/LMS1_TXRF1_1BB_N") (class "Default")
      (node (ref "MN14") (pin "1") (pinfunction "1_1") (pintype "passive"))
      (node (ref "MN16") (pin "1") (pinfunction "1_1") (pintype "passive"))
      (node (ref "T2") (pin "6") (pinfunction "6_6") (pintype "passive"))
    )
    (net (code "32") (name "/LMS1_TXRF1_1BB_P") (class "Default")
      (node (ref "MN10") (pin "1") (pinfunction "1_1") (pintype "passive"))
      (node (ref "MN14") (pin "2") (pinfunction "2_2") (pintype "passive"))
      (node (ref "T2") (pin "4") (pinfunction "4_4") (pintype "passive"))
    )
    (net (code "33") (name "/LMS1_TXRF1_2AB_N") (class "Default")
      (node (ref "IC1") (pin "B10") (pinfunction "pa2on_1_B10") (pintype "passive"))
      (node (ref "MN23") (pin "1") (pinfunction "1_1") (pintype "passive"))
      (node (ref "MN29") (pin "1") (pinfunction "1_1") (pintype "passive"))
      (node (ref "MN32") (pin "1") (pinfunction "1_1") (pintype "passive"))
    )
    (net (code "34") (name "/LMS1_TXRF1_2AB_P") (class "Default")
      (node (ref "IC1") (pin "A9") (pinfunction "pa2op_1_A9") (pintype "passive"))
      (node (ref "MN24") (pin "1") (pinfunction "1_1") (pintype "passive"))
      (node (ref "MN26") (pin "2") (pinfunction "2_2") (pintype "passive"))
      (node (ref "MN29") (pin "2") (pinfunction "2_2") (pintype "passive"))
    )
    (net (code "35") (name "/LMS1_TXRF1_2BB_N") (class "Default")
      (node (ref "MN30") (pin "1") (pinfunction "1_1") (pintype "passive"))
      (node (ref "MN32") (pin "2") (pinfunction "2_2") (pintype "passive"))
      (node (ref "T4") (pin "4") (pinfunction "4_4") (pintype "passive"))
    )
    (net (code "36") (name "/LMS1_TXRF1_2BB_P") (class "Default")
      (node (ref "MN26") (pin "1") (pinfunction "1_1") (pintype "passive"))
      (node (ref "MN30") (pin "2") (pinfunction "2_2") (pintype "passive"))
      (node (ref "T4") (pin "6") (pinfunction "6_6") (pintype "passive"))
    )
    (net (code "37") (name "/LMS1_TXRF2_1AB_N") (class "Default")
      (node (ref "IC1") (pin "C11") (pinfunction "pa1on_2_C11") (pintype "passive"))
      (node (ref "MN11") (pin "2") (pinfunction "2_2") (pintype "passive"))
      (node (ref "MN15") (pin "2") (pinfunction "2_2") (pintype "passive"))
      (node (ref "MN5") (pin "1") (pinfunction "1_1") (pintype "passive"))
    )
    (net (code "38") (name "/LMS1_TXRF2_1AB_P") (class "Default")
      (node (ref "IC1") (pin "B12") (pinfunction "pa1op_2_B12") (pintype "passive"))
      (node (ref "MN11") (pin "1") (pinfunction "1_1") (pintype "passive"))
      (node (ref "MN6") (pin "1") (pinfunction "1_1") (pintype "passive"))
      (node (ref "MN9") (pin "2") (pinfunction "2_2") (pintype "passive"))
    )
    (net (code "39") (name "/LMS1_TXRF2_1BB_N") (class "Default")
      (node (ref "MN12") (pin "1") (pinfunction "1_1") (pintype "passive"))
      (node (ref "MN15") (pin "1") (pinfunction "1_1") (pintype "passive"))
      (node (ref "T1") (pin "6") (pinfunction "6_6") (pintype "passive"))
    )
    (net (code "40") (name "/LMS1_TXRF2_1BB_P") (class "Default")
      (node (ref "MN12") (pin "2") (pinfunction "2_2") (pintype "passive"))
      (node (ref "MN9") (pin "1") (pinfunction "1_1") (pintype "passive"))
      (node (ref "T1") (pin "4") (pinfunction "4_4") (pintype "passive"))
    )
    (net (code "41") (name "/LMS1_TXRF2_2AB_N") (class "Default")
      (node (ref "IC1") (pin "B14") (pinfunction "pa2on_2_B14") (pintype "passive"))
      (node (ref "MN21") (pin "1") (pinfunction "1_1") (pintype "passive"))
      (node (ref "MN27") (pin "1") (pinfunction "1_1") (pintype "passive"))
      (node (ref "MN31") (pin "1") (pinfunction "1_1") (pintype "passive"))
    )
    (net (code "42") (name "/LMS1_TXRF2_2AB_P") (class "Default")
      (node (ref "IC1") (pin "A13") (pinfunction "pa2op_2_A13") (pintype "passive"))
      (node (ref "MN22") (pin "1") (pinfunction "1_1") (pintype "passive"))
      (node (ref "MN25") (pin "2") (pinfunction "2_2") (pintype "passive"))
      (node (ref "MN27") (pin "2") (pinfunction "2_2") (pintype "passive"))
    )
    (net (code "43") (name "/LMS1_TXRF2_2BB_N") (class "Default")
      (node (ref "MN28") (pin "1") (pinfunction "1_1") (pintype "passive"))
      (node (ref "MN31") (pin "2") (pinfunction "2_2") (pintype "passive"))
      (node (ref "T3") (pin "4") (pinfunction "4_4") (pintype "passive"))
    )
    (net (code "44") (name "/LMS1_TXRF2_2BB_P") (class "Default")
      (node (ref "MN25") (pin "1") (pinfunction "1_1") (pintype "passive"))
      (node (ref "MN28") (pin "2") (pinfunction "2_2") (pintype "passive"))
      (node (ref "T3") (pin "6") (pinfunction "6_6") (pintype "passive"))
    )
    (net (code "45") (name "/RFSW_LMS1_RX1_V1") (class "Default")
      (node (ref "C34") (pin "1") (pinfunction "1_1") (pintype "passive"))
      (node (ref "IC8") (pin "10") (pinfunction "V1_10") (pintype "input"))
    )
    (net (code "46") (name "/RFSW_LMS1_RX2_V1") (class "Default")
      (node (ref "C40") (pin "1") (pinfunction "1_1") (pintype "passive"))
      (node (ref "IC10") (pin "10") (pinfunction "V1_10") (pintype "input"))
    )
    (net (code "47") (name "/RFSW_LMS1_TX1_V1") (class "Default")
      (node (ref "C33") (pin "1") (pinfunction "1_1") (pintype "passive"))
      (node (ref "IC7") (pin "10") (pinfunction "V1_10") (pintype "input"))
    )
    (net (code "48") (name "/RFSW_LMS1_TX2_V1") (class "Default")
      (node (ref "C39") (pin "1") (pinfunction "1_1") (pintype "passive"))
      (node (ref "IC9") (pin "10") (pinfunction "V1_10") (pintype "input"))
    )
    (net (code "49") (name "GND") (class "Default")
      (node (ref "C10") (pin "1") (pinfunction "1_1") (pintype "passive"))
      (node (ref "C11") (pin "1") (pinfunction "1_1") (pintype "passive"))
      (node (ref "C12") (pin "1") (pinfunction "1_1") (pintype "passive"))
      (node (ref "C13") (pin "1") (pinfunction "1_1") (pintype "passive"))
      (node (ref "C14") (pin "1") (pinfunction "1_1") (pintype "passive"))
      (node (ref "C17") (pin "1") (pinfunction "1_1") (pintype "passive"))
      (node (ref "C18") (pin "1") (pinfunction "1_1") (pintype "passive"))
      (node (ref "C19") (pin "1") (pinfunction "1_1") (pintype "passive"))
      (node (ref "C20") (pin "1") (pinfunction "1_1") (pintype "passive"))
      (node (ref "C21") (pin "1") (pinfunction "1_1") (pintype "passive"))
      (node (ref "C22") (pin "1") (pinfunction "1_1") (pintype "passive"))
      (node (ref "C23") (pin "1") (pinfunction "1_1") (pintype "passive"))
      (node (ref "C24") (pin "1") (pinfunction "1_1") (pintype "passive"))
      (node (ref "C33") (pin "2") (pinfunction "2_2") (pintype "passive"))
      (node (ref "C34") (pin "2") (pinfunction "2_2") (pintype "passive"))
      (node (ref "C35") (pin "1") (pinfunction "1_1") (pintype "passive"))
      (node (ref "C36") (pin "1") (pinfunction "1_1") (pintype "passive"))
      (node (ref "C39") (pin "2") (pinfunction "2_2") (pintype "passive"))
      (node (ref "C40") (pin "2") (pinfunction "2_2") (pintype "passive"))
      (node (ref "C41") (pin "1") (pinfunction "1_1") (pintype "passive"))
      (node (ref "C42") (pin "1") (pinfunction "1_1") (pintype "passive"))
      (node (ref "C7") (pin "1") (pinfunction "1_1") (pintype "passive"))
      (node (ref "C8") (pin "1") (pinfunction "1_1") (pintype "passive"))
      (node (ref "C9") (pin "1") (pinfunction "1_1") (pintype "passive"))
      (node (ref "ESD1") (pin "2") (pinfunction "2_2") (pintype "passive"))
      (node (ref "ESD2") (pin "2") (pinfunction "2_2") (pintype "passive"))
      (node (ref "IC1") (pin "AJ7") (pinfunction "rfsn_l_RFE_2_AJ7") (pintype "passive"))
      (node (ref "IC1") (pin "AJ9") (pinfunction "rfsp_l_RFE_2_AJ9") (pintype "passive"))
      (node (ref "IC1") (pin "AK12") (pinfunction "rfsn_l_RFE_1_AK12") (pintype "passive"))
      (node (ref "IC1") (pin "AL13") (pinfunction "rfsp_l_RFE_1_AL13") (pintype "passive"))
      (node (ref "IC1") (pin "AM4") (pinfunction "rfgn_w_RFE_2_AM4") (pintype "passive"))
      (node (ref "IC1") (pin "AN3") (pinfunction "rfgp_w_RFE_2_AN3") (pintype "passive"))
      (node (ref "IC1") (pin "AN9") (pinfunction "rfgp_w_RFE_1_AN9") (pintype "passive"))
      (node (ref "IC1") (pin "AP10") (pinfunction "rfgn_w_RFE_1_AP10") (pintype "passive"))
      (node (ref "IC10") (pin "1") (pinfunction "GND_1") (pintype "passive"))
      (node (ref "IC10") (pin "11") (pinfunction "LS_11") (pintype "input"))
      (node (ref "IC10") (pin "3") (pinfunction "GND_3") (pintype "passive"))
      (node (ref "IC10") (pin "4") (pinfunction "GND/NC_4") (pintype "passive"))
      (node (ref "IC10") (pin "6") (pinfunction "GND_6") (pintype "passive"))
      (node (ref "IC10") (pin "7") (pinfunction "GND_7") (pintype "passive"))
      (node (ref "IC10") (pin "9") (pinfunction "DGND_9") (pintype "passive"))
      (node (ref "IC10") (pin "PAD") (pinfunction "PAD_PAD") (pintype "passive"))
      (node (ref "IC7") (pin "1") (pinfunction "GND_1") (pintype "passive"))
      (node (ref "IC7") (pin "11") (pinfunction "LS_11") (pintype "input"))
      (node (ref "IC7") (pin "3") (pinfunction "GND_3") (pintype "passive"))
      (node (ref "IC7") (pin "4") (pinfunction "GND/NC_4") (pintype "passive"))
      (node (ref "IC7") (pin "6") (pinfunction "GND_6") (pintype "passive"))
      (node (ref "IC7") (pin "7") (pinfunction "GND_7") (pintype "passive"))
      (node (ref "IC7") (pin "9") (pinfunction "DGND_9") (pintype "passive"))
      (node (ref "IC7") (pin "PAD") (pinfunction "PAD_PAD") (pintype "passive"))
      (node (ref "IC8") (pin "1") (pinfunction "GND_1") (pintype "passive"))
      (node (ref "IC8") (pin "11") (pinfunction "LS_11") (pintype "input"))
      (node (ref "IC8") (pin "3") (pinfunction "GND_3") (pintype "passive"))
      (node (ref "IC8") (pin "4") (pinfunction "GND/NC_4") (pintype "passive"))
      (node (ref "IC8") (pin "6") (pinfunction "GND_6") (pintype "passive"))
      (node (ref "IC8") (pin "7") (pinfunction "GND_7") (pintype "passive"))
      (node (ref "IC8") (pin "9") (pinfunction "DGND_9") (pintype "passive"))
      (node (ref "IC8") (pin "PAD") (pinfunction "PAD_PAD") (pintype "passive"))
      (node (ref "IC9") (pin "1") (pinfunction "GND_1") (pintype "passive"))
      (node (ref "IC9") (pin "11") (pinfunction "LS_11") (pintype "input"))
      (node (ref "IC9") (pin "3") (pinfunction "GND_3") (pintype "passive"))
      (node (ref "IC9") (pin "4") (pinfunction "GND/NC_4") (pintype "passive"))
      (node (ref "IC9") (pin "6") (pinfunction "GND_6") (pintype "passive"))
      (node (ref "IC9") (pin "7") (pinfunction "GND_7") (pintype "passive"))
      (node (ref "IC9") (pin "9") (pinfunction "DGND_9") (pintype "passive"))
      (node (ref "IC9") (pin "PAD") (pinfunction "PAD_PAD") (pintype "passive"))
      (node (ref "J1") (pin "2") (pinfunction "Y_2") (pintype "passive"))
      (node (ref "J2") (pin "2") (pinfunction "Y_2") (pintype "passive"))
      (node (ref "T1") (pin "2") (pinfunction "2_2") (pintype "passive"))
      (node (ref "T2") (pin "2") (pinfunction "2_2") (pintype "passive"))
      (node (ref "T3") (pin "3") (pinfunction "3_3") (pintype "passive"))
      (node (ref "T4") (pin "3") (pinfunction "3_3") (pintype "passive"))
      (node (ref "T5") (pin "1") (pinfunction "1_1") (pintype "passive"))
      (node (ref "T6") (pin "1") (pinfunction "1_1") (pintype "passive"))
      (node (ref "T7") (pin "2") (pinfunction "2_2") (pintype "passive"))
      (node (ref "T8") (pin "2") (pinfunction "2_2") (pintype "passive"))
    )
    (net (code "50") (name "Net-(C15-Pad2)") (class "Default")
      (node (ref "C15") (pin "2") (pinfunction "2_2") (pintype "passive"))
      (node (ref "T1") (pin "3") (pinfunction "3_3") (pintype "passive"))
    )
    (net (code "51") (name "Net-(C16-Pad2)") (class "Default")
      (node (ref "C16") (pin "2") (pinfunction "2_2") (pintype "passive"))
      (node (ref "T2") (pin "3") (pinfunction "3_3") (pintype "passive"))
    )
    (net (code "52") (name "Net-(C25-Pad2)") (class "Default")
      (node (ref "C25") (pin "2") (pinfunction "2_2") (pintype "passive"))
      (node (ref "T3") (pin "1") (pinfunction "1_1") (pintype "passive"))
    )
    (net (code "53") (name "Net-(C26-Pad2)") (class "Default")
      (node (ref "C26") (pin "2") (pinfunction "2_2") (pintype "passive"))
      (node (ref "T4") (pin "1") (pinfunction "1_1") (pintype "passive"))
    )
    (net (code "54") (name "Net-(C27-Pad2)") (class "Default")
      (node (ref "C27") (pin "2") (pinfunction "2_2") (pintype "passive"))
      (node (ref "T5") (pin "3") (pinfunction "3_3") (pintype "passive"))
    )
    (net (code "55") (name "Net-(C28-Pad2)") (class "Default")
      (node (ref "C28") (pin "2") (pinfunction "2_2") (pintype "passive"))
      (node (ref "T6") (pin "3") (pinfunction "3_3") (pintype "passive"))
    )
    (net (code "56") (name "Net-(C29-Pad2)") (class "Default")
      (node (ref "C29") (pin "2") (pinfunction "2_2") (pintype "passive"))
      (node (ref "T7") (pin "3") (pinfunction "3_3") (pintype "passive"))
    )
    (net (code "57") (name "Net-(C30-Pad2)") (class "Default")
      (node (ref "C30") (pin "2") (pinfunction "2_2") (pintype "passive"))
      (node (ref "T8") (pin "3") (pinfunction "3_3") (pintype "passive"))
    )
    (net (code "58") (name "Net-(IC7-RFC)") (class "Default")
      (node (ref "C31") (pin "1") (pinfunction "1_1") (pintype "passive"))
      (node (ref "IC7") (pin "5") (pinfunction "RFC_5") (pintype "bidirectional"))
    )
    (net (code "59") (name "Net-(IC8-RFC)") (class "Default")
      (node (ref "C32") (pin "2") (pinfunction "2_2") (pintype "passive"))
      (node (ref "IC8") (pin "5") (pinfunction "RFC_5") (pintype "bidirectional"))
    )
    (net (code "60") (name "Net-(IC9-RFC)") (class "Default")
      (node (ref "C37") (pin "1") (pinfunction "1_1") (pintype "passive"))
      (node (ref "IC9") (pin "5") (pinfunction "RFC_5") (pintype "bidirectional"))
    )
    (net (code "61") (name "Net-(IC10-RFC)") (class "Default")
      (node (ref "C38") (pin "2") (pinfunction "2_2") (pintype "passive"))
      (node (ref "IC10") (pin "5") (pinfunction "RFC_5") (pintype "bidirectional"))
    )
    (net (code "62") (name "Net-(MN1-Pad1)") (class "Default")
      (node (ref "MN1") (pin "1") (pinfunction "1_1") (pintype "passive"))
      (node (ref "MN5") (pin "2") (pinfunction "2_2") (pintype "passive"))
    )
    (net (code "63") (name "Net-(MN2-Pad1)") (class "Default")
      (node (ref "MN2") (pin "1") (pinfunction "1_1") (pintype "passive"))
      (node (ref "MN6") (pin "2") (pinfunction "2_2") (pintype "passive"))
    )
    (net (code "64") (name "Net-(MN3-Pad1)") (class "Default")
      (node (ref "MN3") (pin "1") (pinfunction "1_1") (pintype "passive"))
      (node (ref "MN7") (pin "2") (pinfunction "2_2") (pintype "passive"))
    )
    (net (code "65") (name "Net-(MN4-Pad1)") (class "Default")
      (node (ref "MN4") (pin "1") (pinfunction "1_1") (pintype "passive"))
      (node (ref "MN8") (pin "2") (pinfunction "2_2") (pintype "passive"))
    )
    (net (code "66") (name "Net-(MN17-Pad1)") (class "Default")
      (node (ref "MN17") (pin "1") (pinfunction "1_1") (pintype "passive"))
      (node (ref "MN21") (pin "2") (pinfunction "2_2") (pintype "passive"))
    )
    (net (code "67") (name "Net-(MN18-Pad1)") (class "Default")
      (node (ref "MN18") (pin "1") (pinfunction "1_1") (pintype "passive"))
      (node (ref "MN23") (pin "2") (pinfunction "2_2") (pintype "passive"))
    )
    (net (code "68") (name "Net-(MN19-Pad1)") (class "Default")
      (node (ref "MN19") (pin "1") (pinfunction "1_1") (pintype "passive"))
      (node (ref "MN22") (pin "2") (pinfunction "2_2") (pintype "passive"))
    )
    (net (code "69") (name "Net-(MN20-Pad1)") (class "Default")
      (node (ref "MN20") (pin "1") (pinfunction "1_1") (pintype "passive"))
      (node (ref "MN24") (pin "2") (pinfunction "2_2") (pintype "passive"))
    )
    (net (code "70") (name "VCC1P8_LMS1") (class "Default")
      (node (ref "C10") (pin "2") (pinfunction "2_2") (pintype "passive"))
      (node (ref "C11") (pin "2") (pinfunction "2_2") (pintype "passive"))
      (node (ref "C12") (pin "2") (pinfunction "2_2") (pintype "passive"))
      (node (ref "C13") (pin "2") (pinfunction "2_2") (pintype "passive"))
      (node (ref "C14") (pin "2") (pinfunction "2_2") (pintype "passive"))
      (node (ref "C17") (pin "2") (pinfunction "2_2") (pintype "passive"))
      (node (ref "C18") (pin "2") (pinfunction "2_2") (pintype "passive"))
      (node (ref "C19") (pin "2") (pinfunction "2_2") (pintype "passive"))
      (node (ref "C20") (pin "2") (pinfunction "2_2") (pintype "passive"))
      (node (ref "C21") (pin "2") (pinfunction "2_2") (pintype "passive"))
      (node (ref "C22") (pin "2") (pinfunction "2_2") (pintype "passive"))
      (node (ref "C23") (pin "2") (pinfunction "2_2") (pintype "passive"))
      (node (ref "C24") (pin "2") (pinfunction "2_2") (pintype "passive"))
      (node (ref "C7") (pin "2") (pinfunction "2_2") (pintype "passive"))
      (node (ref "C8") (pin "2") (pinfunction "2_2") (pintype "passive"))
      (node (ref "C9") (pin "2") (pinfunction "2_2") (pintype "passive"))
      (node (ref "MN1") (pin "2") (pinfunction "2_2") (pintype "passive"))
      (node (ref "MN17") (pin "2") (pinfunction "2_2") (pintype "passive"))
      (node (ref "MN18") (pin "2") (pinfunction "2_2") (pintype "passive"))
      (node (ref "MN19") (pin "2") (pinfunction "2_2") (pintype "passive"))
      (node (ref "MN2") (pin "2") (pinfunction "2_2") (pintype "passive"))
      (node (ref "MN20") (pin "2") (pinfunction "2_2") (pintype "passive"))
      (node (ref "MN3") (pin "2") (pinfunction "2_2") (pintype "passive"))
      (node (ref "MN4") (pin "2") (pinfunction "2_2") (pintype "passive"))
    )
    (net (code "71") (name "VCC3P3_RF") (class "Default")
      (node (ref "C35") (pin "2") (pinfunction "2_2") (pintype "passive"))
      (node (ref "C36") (pin "2") (pinfunction "2_2") (pintype "passive"))
      (node (ref "C41") (pin "2") (pinfunction "2_2") (pintype "passive"))
      (node (ref "C42") (pin "2") (pinfunction "2_2") (pintype "passive"))
      (node (ref "IC10") (pin "12") (pinfunction "VDD_12") (pintype "power_in"))
      (node (ref "IC7") (pin "12") (pinfunction "VDD_12") (pintype "power_in"))
      (node (ref "IC8") (pin "12") (pinfunction "VDD_12") (pintype "power_in"))
      (node (ref "IC9") (pin "12") (pinfunction "VDD_12") (pintype "power_in"))
    )
    (net (code "72") (name "unconnected-(T3-Pad2)") (class "Default")
      (node (ref "T3") (pin "2") (pinfunction "2_2") (pintype "passive+no_connect"))
    )
    (net (code "73") (name "unconnected-(T4-Pad2)") (class "Default")
      (node (ref "T4") (pin "2") (pinfunction "2_2") (pintype "passive+no_connect"))
    )
    (net (code "74") (name "unconnected-(T5-Pad2)") (class "Default")
      (node (ref "T5") (pin "2") (pinfunction "2_2") (pintype "passive+no_connect"))
    )
    (net (code "75") (name "unconnected-(T6-Pad2)") (class "Default")
      (node (ref "T6") (pin "2") (pinfunction "2_2") (pintype "passive+no_connect"))
    )
  )
)
